# STBlitter_RevA.net
KiCad netlist of a schematic drawn in EAGLE
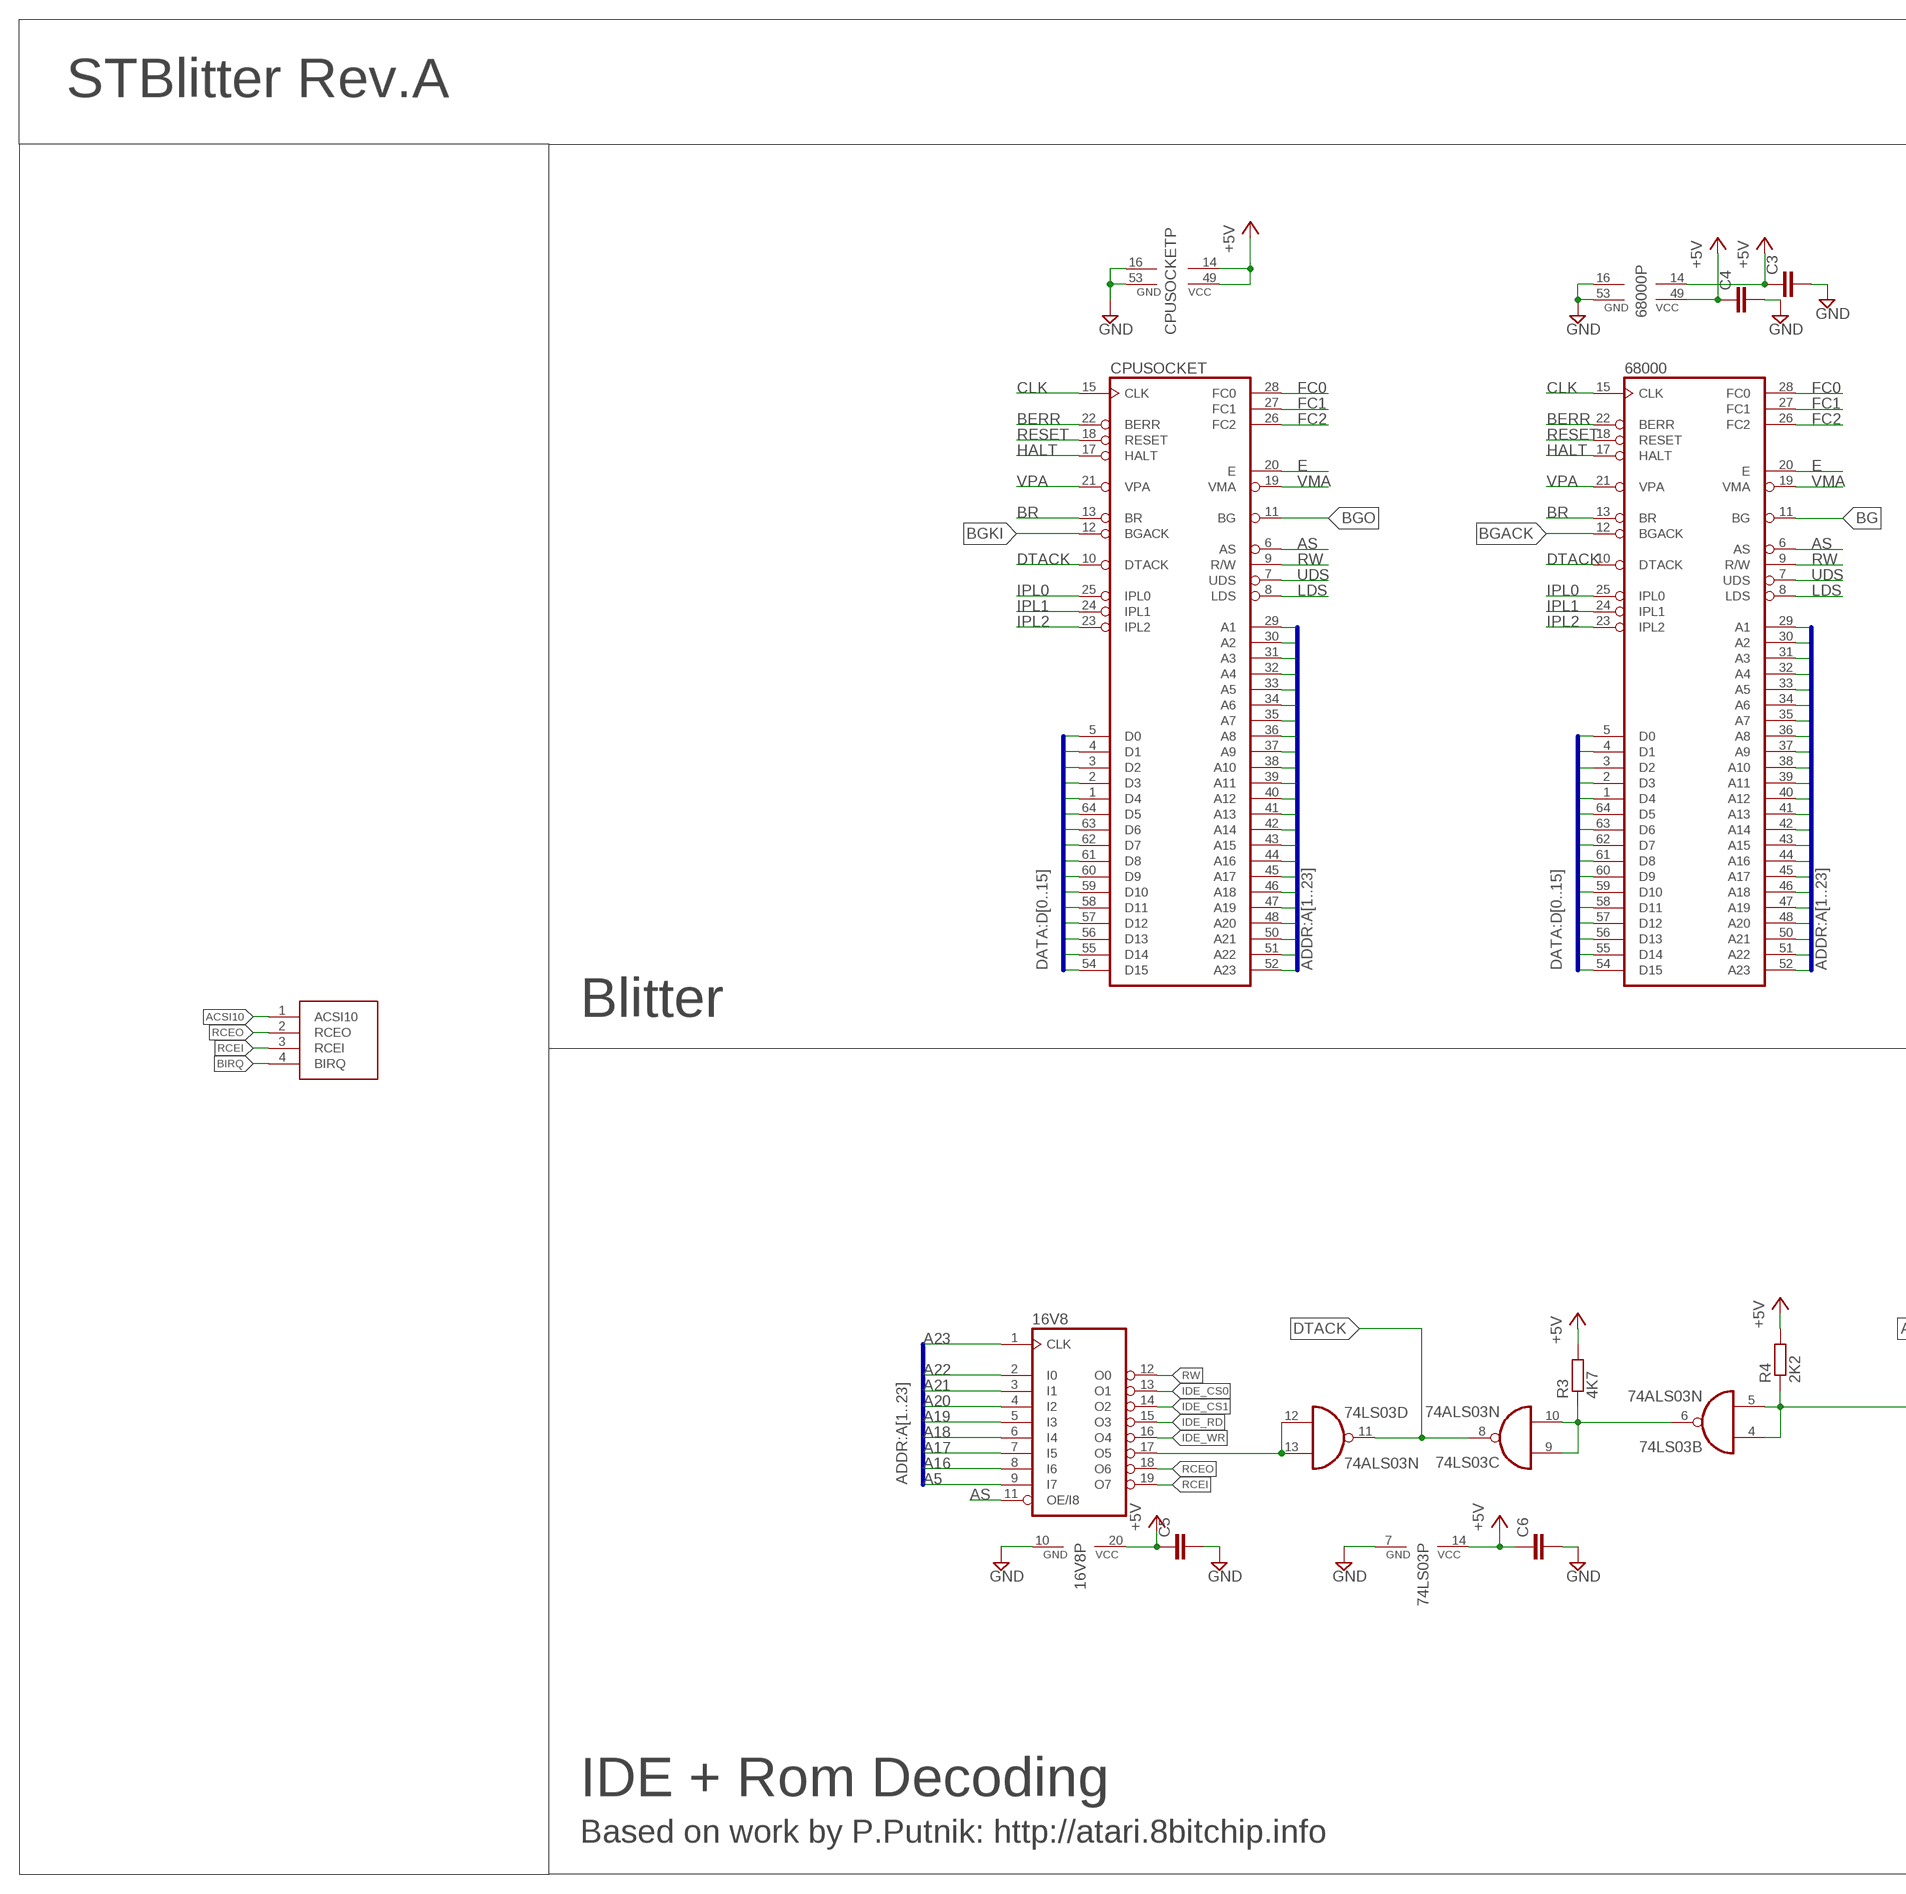
[diagram p0: schematic, sheet 1, part 1 of 2]
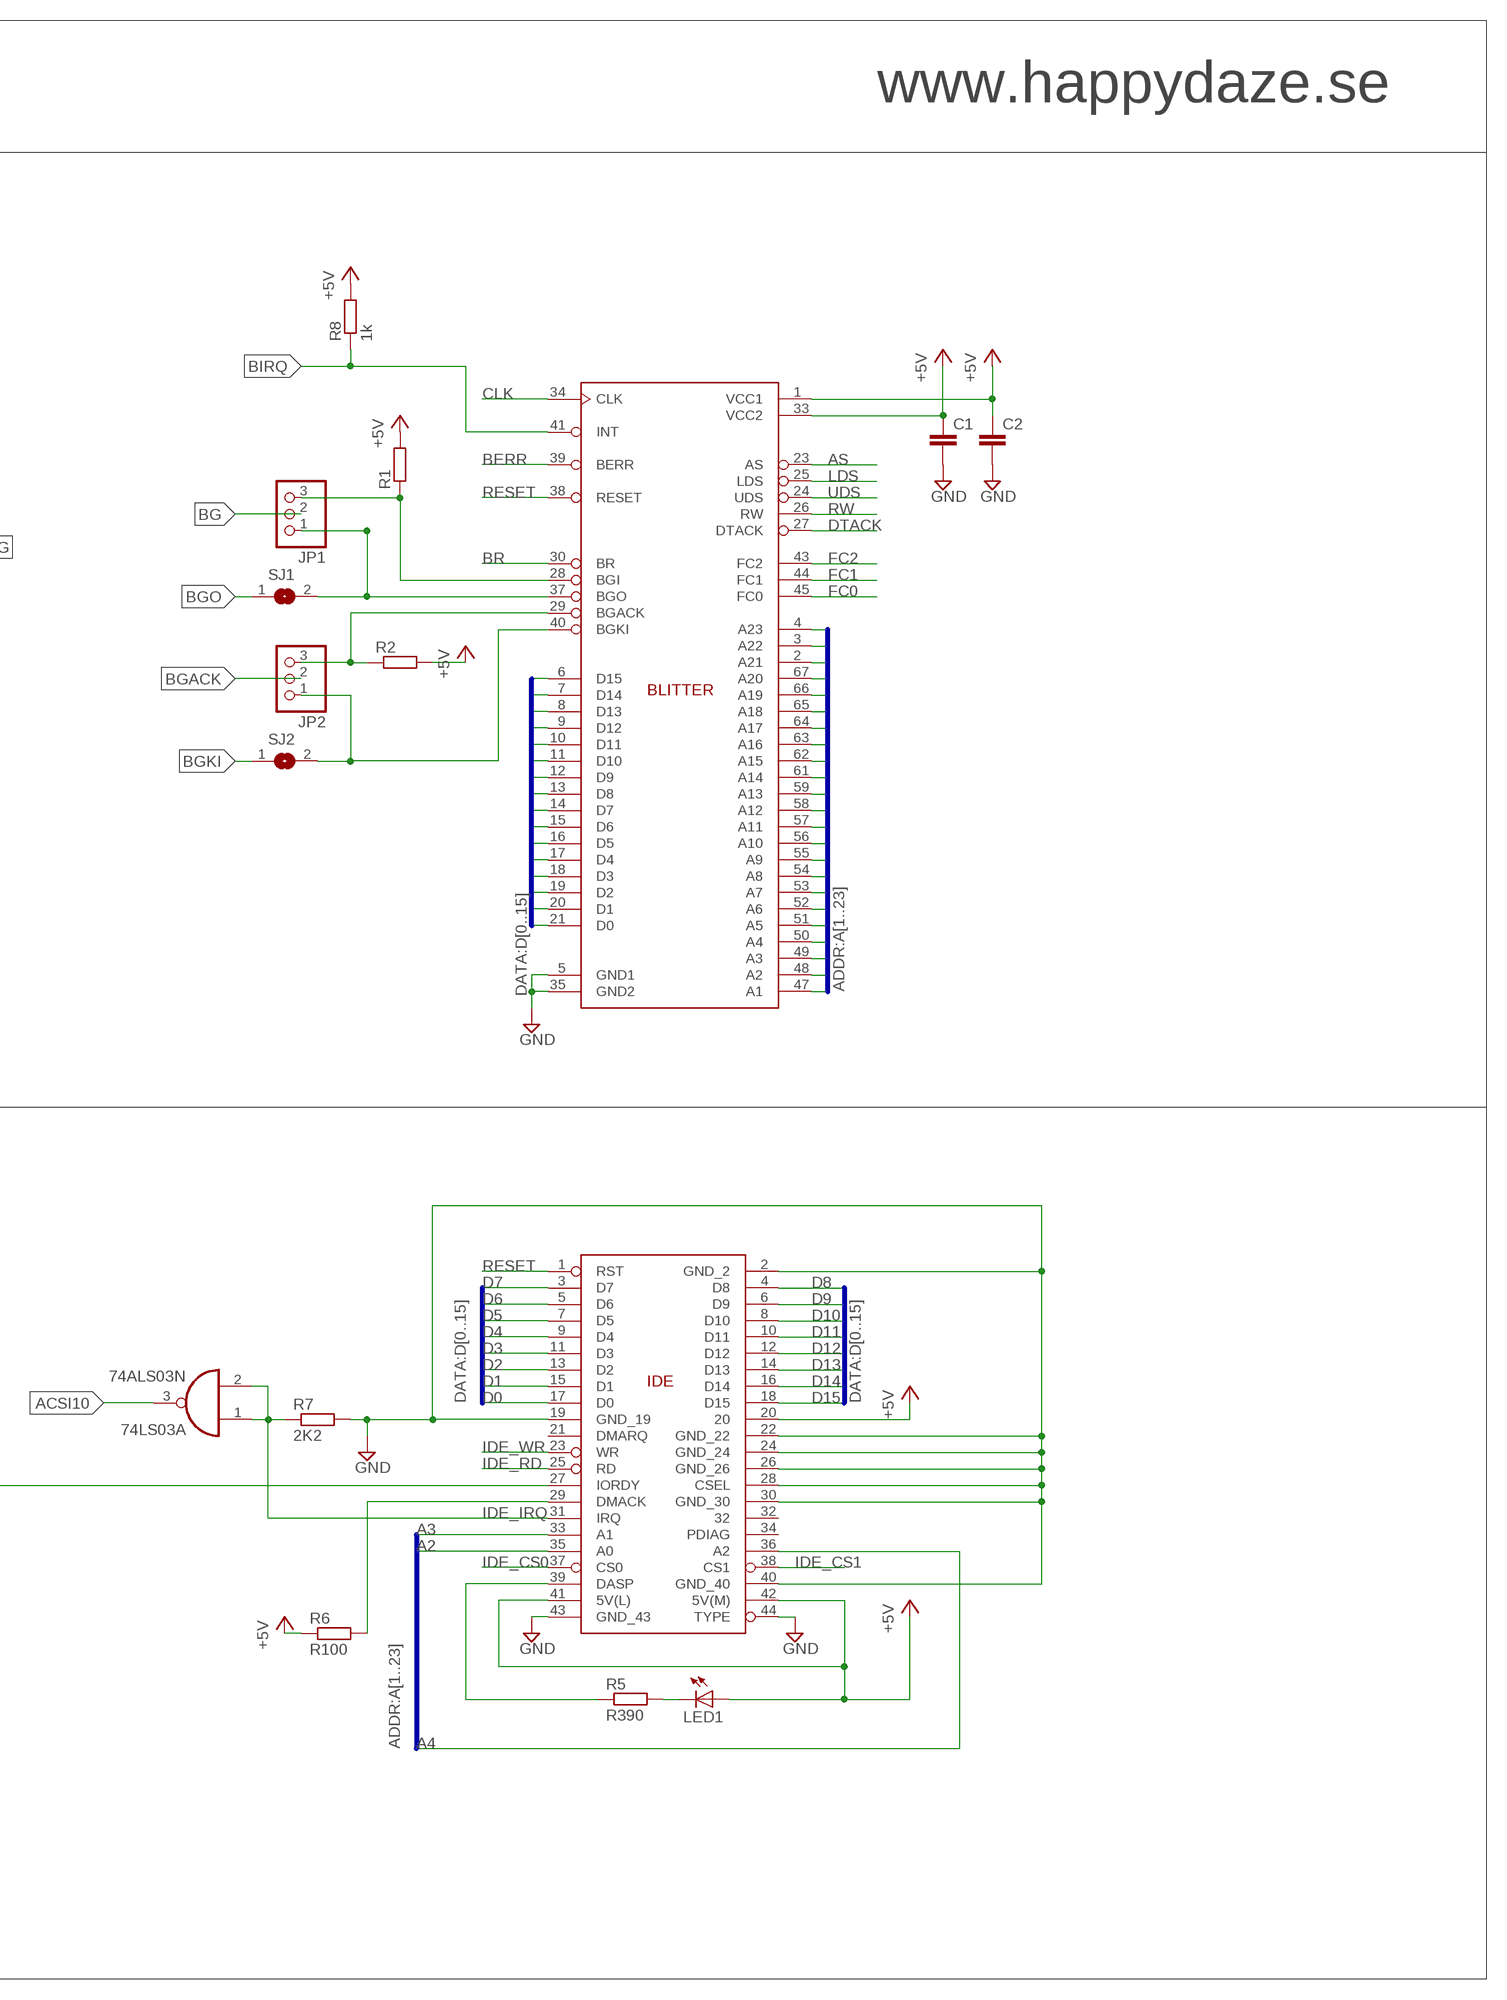
[diagram p1: schematic, sheet 1, part 2 of 2]

(export (version "E")
  (design (tool "Eeschema 10.0.6"))
  (components
    (comp (ref "16V8")
      (value "16V8")
      (footprint "eagle-import:DIL20")
      (fields (field (name "MPN") "GAL16V8D-7LPN"))
      (libsource (lib "eagle-import") (part "16V8"))
    )
    (comp (ref "74LS03")
      (value "74ALS03N")
      (footprint "eagle-import:DIL14")
      (libsource (lib "eagle-import") (part "7403NALS"))
    )
    (comp (ref "68000")
      (value "MC68000P")
      (footprint "eagle-import:DIL64")
      (libsource (lib "eagle-import") (part "micro-mc68000_288_MC68000P"))
    )
    (comp (ref "C1")
      (value "C-EU050-025X075")
      (footprint "eagle-import:C050-025X075")
      (libsource (lib "eagle-import") (part "C-EU050-025X075"))
    )
    (comp (ref "C2")
      (value "C-EU050-025X075")
      (footprint "eagle-import:C050-025X075")
      (libsource (lib "eagle-import") (part "C-EU050-025X075"))
    )
    (comp (ref "C3")
      (value "C-EU050-025X075")
      (footprint "eagle-import:C050-025X075")
      (libsource (lib "eagle-import") (part "C-EU050-025X075"))
    )
    (comp (ref "C4")
      (value "C-EU050-025X075")
      (footprint "eagle-import:C050-025X075")
      (libsource (lib "eagle-import") (part "C-EU050-025X075"))
    )
    (comp (ref "C5")
      (value "C-EU050-025X075")
      (footprint "eagle-import:C050-025X075")
      (libsource (lib "eagle-import") (part "C-EU050-025X075"))
    )
    (comp (ref "C6")
      (value "C-EU050-025X075")
      (footprint "eagle-import:C050-025X075")
      (libsource (lib "eagle-import") (part "C-EU050-025X075"))
    )
    (comp (ref "CFCARD")
      (value "IDE44_CON")
      (footprint "eagle-import:IDE44_CON")
      (libsource (lib "eagle-import") (part "IDE44_CON"))
    )
    (comp (ref "CPUSOCKET")
      (value "MC68000P")
      (footprint "eagle-import:DIL64")
      (libsource (lib "eagle-import") (part "MC68000P"))
    )
    (comp (ref "JP1")
      (value "PINHD-1X3")
      (footprint "eagle-import:1X03")
      (libsource (lib "eagle-import") (part "PINHD-1X3"))
    )
    (comp (ref "JP2")
      (value "PINHD-1X3")
      (footprint "eagle-import:1X03")
      (libsource (lib "eagle-import") (part "PINHD-1X3"))
    )
    (comp (ref "LED1")
      (value "LED3MM")
      (footprint "eagle-import:LED3MM")
      (libsource (lib "eagle-import") (part "LED3MM"))
    )
    (comp (ref "R1")
      (value "R-EU_0207/12")
      (footprint "eagle-import:0207_12")
      (libsource (lib "eagle-import") (part "R-EU_0207/12"))
    )
    (comp (ref "R2")
      (value "R-EU_0207/12")
      (footprint "eagle-import:0207_12")
      (libsource (lib "eagle-import") (part "R-EU_0207/12"))
    )
    (comp (ref "R3")
      (value "4K7")
      (footprint "eagle-import:0207_12")
      (libsource (lib "eagle-import") (part "R-EU_0207/12"))
    )
    (comp (ref "R4")
      (value "2K2")
      (footprint "eagle-import:0207_12")
      (libsource (lib "eagle-import") (part "R-EU_0207/12"))
    )
    (comp (ref "R5")
      (value "R390")
      (footprint "eagle-import:0207_12")
      (libsource (lib "eagle-import") (part "R-EU_0207/12"))
    )
    (comp (ref "R6")
      (value "R100")
      (footprint "eagle-import:0207_12")
      (libsource (lib "eagle-import") (part "R-EU_0207/12"))
    )
    (comp (ref "R7")
      (value "2K2")
      (footprint "eagle-import:0207_12")
      (libsource (lib "eagle-import") (part "R-EU_0207/12"))
    )
    (comp (ref "R8")
      (value "1k")
      (footprint "eagle-import:0207_12")
      (libsource (lib "eagle-import") (part "R-EU_0207/12"))
    )
    (comp (ref "SJ1") (value "SJ") (footprint "eagle-import:SJ") (libsource (lib "eagle-import") (part "SJ")))
    (comp (ref "SJ2") (value "SJ") (footprint "eagle-import:SJ") (libsource (lib "eagle-import") (part "SJ")))
    (comp (ref "U$1")
      (value "STBLITTER")
      (footprint "eagle-import:S68")
      (libsource (lib "eagle-import") (part "STBLITTER"))
    )
    (comp (ref "U$2")
      (value "XCON")
      (footprint "eagle-import:XCON")
      (libsource (lib "eagle-import") (part "XCON"))
    )
  )
  (nets
    (net (code "40") (name "+5V") (class "Default")
      (node (ref "16V8") (pin "20") (pinfunction "VCC_20") (pintype "power_in"))
      (node (ref "68000") (pin "14") (pinfunction "VCC_14") (pintype "power_in"))
      (node (ref "68000") (pin "49") (pinfunction "VCC_49") (pintype "power_in"))
      (node (ref "74LS03") (pin "14") (pinfunction "VCC_14") (pintype "power_in"))
      (node (ref "C1") (pin "1") (pinfunction "1_1") (pintype "passive"))
      (node (ref "C2") (pin "1") (pinfunction "1_1") (pintype "passive"))
      (node (ref "C3") (pin "1") (pinfunction "1_1") (pintype "passive"))
      (node (ref "C4") (pin "1") (pinfunction "1_1") (pintype "passive"))
      (node (ref "C5") (pin "1") (pinfunction "1_1") (pintype "passive"))
      (node (ref "C6") (pin "1") (pinfunction "1_1") (pintype "passive"))
      (node (ref "CFCARD") (pin "20") (pinfunction "20_20") (pintype "bidirectional"))
      (node (ref "CFCARD") (pin "41") (pinfunction "5V(L)_41") (pintype "bidirectional"))
      (node (ref "CFCARD") (pin "42") (pinfunction "5V(M)_42") (pintype "bidirectional"))
      (node (ref "CPUSOCKET") (pin "14") (pinfunction "VCC_14") (pintype "power_in"))
      (node (ref "CPUSOCKET") (pin "49") (pinfunction "VCC_49") (pintype "power_in"))
      (node (ref "LED1") (pin "A") (pinfunction "A_A") (pintype "passive"))
      (node (ref "R1") (pin "2") (pinfunction "2_2") (pintype "passive"))
      (node (ref "R2") (pin "2") (pinfunction "2_2") (pintype "passive"))
      (node (ref "R3") (pin "2") (pinfunction "2_2") (pintype "passive"))
      (node (ref "R4") (pin "2") (pinfunction "2_2") (pintype "passive"))
      (node (ref "R6") (pin "1") (pinfunction "1_1") (pintype "passive"))
      (node (ref "R8") (pin "2") (pinfunction "2_2") (pintype "passive"))
      (node (ref "U$1") (pin "1") (pinfunction "VCC1_1") (pintype "power_in"))
      (node (ref "U$1") (pin "33") (pinfunction "VCC2_33") (pintype "power_in"))
    )
    (net (code "41") (name "/A1") (class "Default")
      (node (ref "68000") (pin "29") (pinfunction "A1_29") (pintype "output"))
      (node (ref "CPUSOCKET") (pin "29") (pinfunction "A1_29") (pintype "output"))
      (node (ref "U$1") (pin "47") (pinfunction "A1_47") (pintype "bidirectional"))
    )
    (net (code "42") (name "/A2") (class "Default")
      (node (ref "68000") (pin "30") (pinfunction "A2_30") (pintype "output"))
      (node (ref "CFCARD") (pin "35") (pinfunction "A0_35") (pintype "bidirectional"))
      (node (ref "CPUSOCKET") (pin "30") (pinfunction "A2_30") (pintype "output"))
      (node (ref "U$1") (pin "48") (pinfunction "A2_48") (pintype "bidirectional"))
    )
    (net (code "43") (name "/A3") (class "Default")
      (node (ref "68000") (pin "31") (pinfunction "A3_31") (pintype "output"))
      (node (ref "CFCARD") (pin "33") (pinfunction "A1_33") (pintype "bidirectional"))
      (node (ref "CPUSOCKET") (pin "31") (pinfunction "A3_31") (pintype "output"))
      (node (ref "U$1") (pin "49") (pinfunction "A3_49") (pintype "bidirectional"))
    )
    (net (code "44") (name "/A4") (class "Default")
      (node (ref "68000") (pin "32") (pinfunction "A4_32") (pintype "output"))
      (node (ref "CFCARD") (pin "36") (pinfunction "A2_36") (pintype "bidirectional"))
      (node (ref "CPUSOCKET") (pin "32") (pinfunction "A4_32") (pintype "output"))
      (node (ref "U$1") (pin "50") (pinfunction "A4_50") (pintype "bidirectional"))
    )
    (net (code "45") (name "/A5") (class "Default")
      (node (ref "16V8") (pin "9") (pinfunction "I7_9") (pintype "input"))
      (node (ref "68000") (pin "33") (pinfunction "A5_33") (pintype "output"))
      (node (ref "CPUSOCKET") (pin "33") (pinfunction "A5_33") (pintype "output"))
      (node (ref "U$1") (pin "51") (pinfunction "A5_51") (pintype "bidirectional"))
    )
    (net (code "46") (name "/A6") (class "Default")
      (node (ref "68000") (pin "34") (pinfunction "A6_34") (pintype "output"))
      (node (ref "CPUSOCKET") (pin "34") (pinfunction "A6_34") (pintype "output"))
      (node (ref "U$1") (pin "52") (pinfunction "A6_52") (pintype "bidirectional"))
    )
    (net (code "47") (name "/A7") (class "Default")
      (node (ref "68000") (pin "35") (pinfunction "A7_35") (pintype "output"))
      (node (ref "CPUSOCKET") (pin "35") (pinfunction "A7_35") (pintype "output"))
      (node (ref "U$1") (pin "53") (pinfunction "A7_53") (pintype "bidirectional"))
    )
    (net (code "48") (name "/A8") (class "Default")
      (node (ref "68000") (pin "36") (pinfunction "A8_36") (pintype "output"))
      (node (ref "CPUSOCKET") (pin "36") (pinfunction "A8_36") (pintype "output"))
      (node (ref "U$1") (pin "54") (pinfunction "A8_54") (pintype "bidirectional"))
    )
    (net (code "49") (name "/A9") (class "Default")
      (node (ref "68000") (pin "37") (pinfunction "A9_37") (pintype "output"))
      (node (ref "CPUSOCKET") (pin "37") (pinfunction "A9_37") (pintype "output"))
      (node (ref "U$1") (pin "55") (pinfunction "A9_55") (pintype "bidirectional"))
    )
    (net (code "50") (name "/A10") (class "Default")
      (node (ref "68000") (pin "38") (pinfunction "A10_38") (pintype "output"))
      (node (ref "CPUSOCKET") (pin "38") (pinfunction "A10_38") (pintype "output"))
      (node (ref "U$1") (pin "56") (pinfunction "A10_56") (pintype "bidirectional"))
    )
    (net (code "51") (name "/A11") (class "Default")
      (node (ref "68000") (pin "39") (pinfunction "A11_39") (pintype "output"))
      (node (ref "CPUSOCKET") (pin "39") (pinfunction "A11_39") (pintype "output"))
      (node (ref "U$1") (pin "57") (pinfunction "A11_57") (pintype "bidirectional"))
    )
    (net (code "52") (name "/A12") (class "Default")
      (node (ref "68000") (pin "40") (pinfunction "A12_40") (pintype "output"))
      (node (ref "CPUSOCKET") (pin "40") (pinfunction "A12_40") (pintype "output"))
      (node (ref "U$1") (pin "58") (pinfunction "A12_58") (pintype "bidirectional"))
    )
    (net (code "53") (name "/A13") (class "Default")
      (node (ref "68000") (pin "41") (pinfunction "A13_41") (pintype "output"))
      (node (ref "CPUSOCKET") (pin "41") (pinfunction "A13_41") (pintype "output"))
      (node (ref "U$1") (pin "59") (pinfunction "A13_59") (pintype "bidirectional"))
    )
    (net (code "54") (name "/A14") (class "Default")
      (node (ref "68000") (pin "42") (pinfunction "A14_42") (pintype "output"))
      (node (ref "CPUSOCKET") (pin "42") (pinfunction "A14_42") (pintype "output"))
      (node (ref "U$1") (pin "61") (pinfunction "A14_61") (pintype "bidirectional"))
    )
    (net (code "55") (name "/A15") (class "Default")
      (node (ref "68000") (pin "43") (pinfunction "A15_43") (pintype "output"))
      (node (ref "CPUSOCKET") (pin "43") (pinfunction "A15_43") (pintype "output"))
      (node (ref "U$1") (pin "62") (pinfunction "A15_62") (pintype "bidirectional"))
    )
    (net (code "56") (name "/A16") (class "Default")
      (node (ref "16V8") (pin "8") (pinfunction "I6_8") (pintype "input"))
      (node (ref "68000") (pin "44") (pinfunction "A16_44") (pintype "output"))
      (node (ref "CPUSOCKET") (pin "44") (pinfunction "A16_44") (pintype "output"))
      (node (ref "U$1") (pin "63") (pinfunction "A16_63") (pintype "bidirectional"))
    )
    (net (code "57") (name "/A17") (class "Default")
      (node (ref "16V8") (pin "7") (pinfunction "I5_7") (pintype "input"))
      (node (ref "68000") (pin "45") (pinfunction "A17_45") (pintype "output"))
      (node (ref "CPUSOCKET") (pin "45") (pinfunction "A17_45") (pintype "output"))
      (node (ref "U$1") (pin "64") (pinfunction "A17_64") (pintype "bidirectional"))
    )
    (net (code "58") (name "/A18") (class "Default")
      (node (ref "16V8") (pin "6") (pinfunction "I4_6") (pintype "input"))
      (node (ref "68000") (pin "46") (pinfunction "A18_46") (pintype "output"))
      (node (ref "CPUSOCKET") (pin "46") (pinfunction "A18_46") (pintype "output"))
      (node (ref "U$1") (pin "65") (pinfunction "A18_65") (pintype "bidirectional"))
    )
    (net (code "59") (name "/A19") (class "Default")
      (node (ref "16V8") (pin "5") (pinfunction "I3_5") (pintype "input"))
      (node (ref "68000") (pin "47") (pinfunction "A19_47") (pintype "output"))
      (node (ref "CPUSOCKET") (pin "47") (pinfunction "A19_47") (pintype "output"))
      (node (ref "U$1") (pin "66") (pinfunction "A19_66") (pintype "bidirectional"))
    )
    (net (code "60") (name "/A20") (class "Default")
      (node (ref "16V8") (pin "4") (pinfunction "I2_4") (pintype "input"))
      (node (ref "68000") (pin "48") (pinfunction "A20_48") (pintype "output"))
      (node (ref "CPUSOCKET") (pin "48") (pinfunction "A20_48") (pintype "output"))
      (node (ref "U$1") (pin "67") (pinfunction "A20_67") (pintype "bidirectional"))
    )
    (net (code "61") (name "/A21") (class "Default")
      (node (ref "16V8") (pin "3") (pinfunction "I1_3") (pintype "input"))
      (node (ref "68000") (pin "50") (pinfunction "A21_50") (pintype "output"))
      (node (ref "CPUSOCKET") (pin "50") (pinfunction "A21_50") (pintype "output"))
      (node (ref "U$1") (pin "2") (pinfunction "A21_2") (pintype "bidirectional"))
    )
    (net (code "62") (name "/A22") (class "Default")
      (node (ref "16V8") (pin "2") (pinfunction "I0_2") (pintype "input"))
      (node (ref "68000") (pin "51") (pinfunction "A22_51") (pintype "output"))
      (node (ref "CPUSOCKET") (pin "51") (pinfunction "A22_51") (pintype "output"))
      (node (ref "U$1") (pin "3") (pinfunction "A22_3") (pintype "bidirectional"))
    )
    (net (code "63") (name "/A23") (class "Default")
      (node (ref "16V8") (pin "1") (pinfunction "CLK_1") (pintype "input"))
      (node (ref "68000") (pin "52") (pinfunction "A23_52") (pintype "output"))
      (node (ref "CPUSOCKET") (pin "52") (pinfunction "A23_52") (pintype "output"))
      (node (ref "U$1") (pin "4") (pinfunction "A23_4") (pintype "bidirectional"))
    )
    (net (code "65") (name "/AS") (class "Default")
      (node (ref "16V8") (pin "11") (pinfunction "OE/I8_11") (pintype "input"))
      (node (ref "68000") (pin "6") (pinfunction "AS_6") (pintype "output"))
      (node (ref "CPUSOCKET") (pin "6") (pinfunction "AS_6") (pintype "output"))
      (node (ref "U$1") (pin "23") (pinfunction "AS_23") (pintype "bidirectional"))
    )
    (net (code "66") (name "/BERR") (class "Default")
      (node (ref "68000") (pin "22") (pinfunction "BERR_22") (pintype "input"))
      (node (ref "CPUSOCKET") (pin "22") (pinfunction "BERR_22") (pintype "input"))
      (node (ref "U$1") (pin "39") (pinfunction "BERR_39") (pintype "bidirectional"))
    )
    (net (code "67") (name "/BR") (class "Default")
      (node (ref "68000") (pin "13") (pinfunction "BR_13") (pintype "input"))
      (node (ref "CPUSOCKET") (pin "13") (pinfunction "BR_13") (pintype "input"))
      (node (ref "U$1") (pin "30") (pinfunction "BR_30") (pintype "bidirectional"))
    )
    (net (code "68") (name "/CLK") (class "Default")
      (node (ref "68000") (pin "15") (pinfunction "CLK_15") (pintype "input"))
      (node (ref "CPUSOCKET") (pin "15") (pinfunction "CLK_15") (pintype "input"))
      (node (ref "U$1") (pin "34") (pinfunction "CLK_34") (pintype "bidirectional"))
    )
    (net (code "69") (name "/D0") (class "Default")
      (node (ref "68000") (pin "5") (pinfunction "D0_5") (pintype "bidirectional"))
      (node (ref "CFCARD") (pin "17") (pinfunction "D0_17") (pintype "bidirectional"))
      (node (ref "CPUSOCKET") (pin "5") (pinfunction "D0_5") (pintype "bidirectional"))
      (node (ref "U$1") (pin "21") (pinfunction "D0_21") (pintype "bidirectional"))
    )
    (net (code "70") (name "/D1") (class "Default")
      (node (ref "68000") (pin "4") (pinfunction "D1_4") (pintype "bidirectional"))
      (node (ref "CFCARD") (pin "15") (pinfunction "D1_15") (pintype "bidirectional"))
      (node (ref "CPUSOCKET") (pin "4") (pinfunction "D1_4") (pintype "bidirectional"))
      (node (ref "U$1") (pin "20") (pinfunction "D1_20") (pintype "bidirectional"))
    )
    (net (code "71") (name "/D2") (class "Default")
      (node (ref "68000") (pin "3") (pinfunction "D2_3") (pintype "bidirectional"))
      (node (ref "CFCARD") (pin "13") (pinfunction "D2_13") (pintype "bidirectional"))
      (node (ref "CPUSOCKET") (pin "3") (pinfunction "D2_3") (pintype "bidirectional"))
      (node (ref "U$1") (pin "19") (pinfunction "D2_19") (pintype "bidirectional"))
    )
    (net (code "72") (name "/D3") (class "Default")
      (node (ref "68000") (pin "2") (pinfunction "D3_2") (pintype "bidirectional"))
      (node (ref "CFCARD") (pin "11") (pinfunction "D3_11") (pintype "bidirectional"))
      (node (ref "CPUSOCKET") (pin "2") (pinfunction "D3_2") (pintype "bidirectional"))
      (node (ref "U$1") (pin "18") (pinfunction "D3_18") (pintype "bidirectional"))
    )
    (net (code "73") (name "/D4") (class "Default")
      (node (ref "68000") (pin "1") (pinfunction "D4_1") (pintype "bidirectional"))
      (node (ref "CFCARD") (pin "9") (pinfunction "D4_9") (pintype "bidirectional"))
      (node (ref "CPUSOCKET") (pin "1") (pinfunction "D4_1") (pintype "bidirectional"))
      (node (ref "U$1") (pin "17") (pinfunction "D4_17") (pintype "bidirectional"))
    )
    (net (code "74") (name "/D5") (class "Default")
      (node (ref "68000") (pin "64") (pinfunction "D5_64") (pintype "bidirectional"))
      (node (ref "CFCARD") (pin "7") (pinfunction "D5_7") (pintype "bidirectional"))
      (node (ref "CPUSOCKET") (pin "64") (pinfunction "D5_64") (pintype "bidirectional"))
      (node (ref "U$1") (pin "16") (pinfunction "D5_16") (pintype "bidirectional"))
    )
    (net (code "75") (name "/D6") (class "Default")
      (node (ref "68000") (pin "63") (pinfunction "D6_63") (pintype "bidirectional"))
      (node (ref "CFCARD") (pin "5") (pinfunction "D6_5") (pintype "bidirectional"))
      (node (ref "CPUSOCKET") (pin "63") (pinfunction "D6_63") (pintype "bidirectional"))
      (node (ref "U$1") (pin "15") (pinfunction "D6_15") (pintype "bidirectional"))
    )
    (net (code "76") (name "/D7") (class "Default")
      (node (ref "68000") (pin "62") (pinfunction "D7_62") (pintype "bidirectional"))
      (node (ref "CFCARD") (pin "3") (pinfunction "D7_3") (pintype "bidirectional"))
      (node (ref "CPUSOCKET") (pin "62") (pinfunction "D7_62") (pintype "bidirectional"))
      (node (ref "U$1") (pin "14") (pinfunction "D7_14") (pintype "bidirectional"))
    )
    (net (code "77") (name "/D8") (class "Default")
      (node (ref "68000") (pin "61") (pinfunction "D8_61") (pintype "bidirectional"))
      (node (ref "CFCARD") (pin "4") (pinfunction "D8_4") (pintype "bidirectional"))
      (node (ref "CPUSOCKET") (pin "61") (pinfunction "D8_61") (pintype "bidirectional"))
      (node (ref "U$1") (pin "13") (pinfunction "D8_13") (pintype "bidirectional"))
    )
    (net (code "78") (name "/D9") (class "Default")
      (node (ref "68000") (pin "60") (pinfunction "D9_60") (pintype "bidirectional"))
      (node (ref "CFCARD") (pin "6") (pinfunction "D9_6") (pintype "bidirectional"))
      (node (ref "CPUSOCKET") (pin "60") (pinfunction "D9_60") (pintype "bidirectional"))
      (node (ref "U$1") (pin "12") (pinfunction "D9_12") (pintype "bidirectional"))
    )
    (net (code "79") (name "/D10") (class "Default")
      (node (ref "68000") (pin "59") (pinfunction "D10_59") (pintype "bidirectional"))
      (node (ref "CFCARD") (pin "8") (pinfunction "D10_8") (pintype "bidirectional"))
      (node (ref "CPUSOCKET") (pin "59") (pinfunction "D10_59") (pintype "bidirectional"))
      (node (ref "U$1") (pin "11") (pinfunction "D10_11") (pintype "bidirectional"))
    )
    (net (code "80") (name "/D11") (class "Default")
      (node (ref "68000") (pin "58") (pinfunction "D11_58") (pintype "bidirectional"))
      (node (ref "CFCARD") (pin "10") (pinfunction "D11_10") (pintype "bidirectional"))
      (node (ref "CPUSOCKET") (pin "58") (pinfunction "D11_58") (pintype "bidirectional"))
      (node (ref "U$1") (pin "10") (pinfunction "D11_10") (pintype "bidirectional"))
    )
    (net (code "81") (name "/D12") (class "Default")
      (node (ref "68000") (pin "57") (pinfunction "D12_57") (pintype "bidirectional"))
      (node (ref "CFCARD") (pin "12") (pinfunction "D12_12") (pintype "bidirectional"))
      (node (ref "CPUSOCKET") (pin "57") (pinfunction "D12_57") (pintype "bidirectional"))
      (node (ref "U$1") (pin "9") (pinfunction "D12_9") (pintype "bidirectional"))
    )
    (net (code "82") (name "/D13") (class "Default")
      (node (ref "68000") (pin "56") (pinfunction "D13_56") (pintype "bidirectional"))
      (node (ref "CFCARD") (pin "14") (pinfunction "D13_14") (pintype "bidirectional"))
      (node (ref "CPUSOCKET") (pin "56") (pinfunction "D13_56") (pintype "bidirectional"))
      (node (ref "U$1") (pin "8") (pinfunction "D13_8") (pintype "bidirectional"))
    )
    (net (code "83") (name "/D14") (class "Default")
      (node (ref "68000") (pin "55") (pinfunction "D14_55") (pintype "bidirectional"))
      (node (ref "CFCARD") (pin "16") (pinfunction "D14_16") (pintype "bidirectional"))
      (node (ref "CPUSOCKET") (pin "55") (pinfunction "D14_55") (pintype "bidirectional"))
      (node (ref "U$1") (pin "7") (pinfunction "D14_7") (pintype "bidirectional"))
    )
    (net (code "84") (name "/D15") (class "Default")
      (node (ref "68000") (pin "54") (pinfunction "D15_54") (pintype "bidirectional"))
      (node (ref "CFCARD") (pin "18") (pinfunction "D15_18") (pintype "bidirectional"))
      (node (ref "CPUSOCKET") (pin "54") (pinfunction "D15_54") (pintype "bidirectional"))
      (node (ref "U$1") (pin "6") (pinfunction "D15_6") (pintype "bidirectional"))
    )
    (net (code "86") (name "/E") (class "Default")
      (node (ref "68000") (pin "20") (pinfunction "E_20") (pintype "output"))
      (node (ref "CPUSOCKET") (pin "20") (pinfunction "E_20") (pintype "output"))
    )
    (net (code "87") (name "/FC0") (class "Default")
      (node (ref "68000") (pin "28") (pinfunction "FC0_28") (pintype "output"))
      (node (ref "CPUSOCKET") (pin "28") (pinfunction "FC0_28") (pintype "output"))
      (node (ref "U$1") (pin "45") (pinfunction "FC0_45") (pintype "bidirectional"))
    )
    (net (code "88") (name "/FC1") (class "Default")
      (node (ref "68000") (pin "27") (pinfunction "FC1_27") (pintype "output"))
      (node (ref "CPUSOCKET") (pin "27") (pinfunction "FC1_27") (pintype "output"))
      (node (ref "U$1") (pin "44") (pinfunction "FC1_44") (pintype "bidirectional"))
    )
    (net (code "89") (name "/FC2") (class "Default")
      (node (ref "68000") (pin "26") (pinfunction "FC2_26") (pintype "output"))
      (node (ref "CPUSOCKET") (pin "26") (pinfunction "FC2_26") (pintype "output"))
      (node (ref "U$1") (pin "43") (pinfunction "FC2_43") (pintype "bidirectional"))
    )
    (net (code "90") (name "/HALT") (class "Default")
      (node (ref "68000") (pin "17") (pinfunction "HALT_17") (pintype "bidirectional"))
      (node (ref "CPUSOCKET") (pin "17") (pinfunction "HALT_17") (pintype "bidirectional"))
    )
    (net (code "91") (name "/IDE_IRQ") (class "Default")
      (node (ref "74LS03") (pin "1") (pinfunction "I0_1") (pintype "input"))
      (node (ref "74LS03") (pin "2") (pinfunction "I1_2") (pintype "input"))
      (node (ref "CFCARD") (pin "31") (pinfunction "IRQ_31") (pintype "bidirectional"))
      (node (ref "R7") (pin "1") (pinfunction "1_1") (pintype "passive"))
    )
    (net (code "92") (name "/IPL0") (class "Default")
      (node (ref "68000") (pin "25") (pinfunction "IPL0_25") (pintype "input"))
      (node (ref "CPUSOCKET") (pin "25") (pinfunction "IPL0_25") (pintype "input"))
    )
    (net (code "93") (name "/IPL1") (class "Default")
      (node (ref "68000") (pin "24") (pinfunction "IPL1_24") (pintype "input"))
      (node (ref "CPUSOCKET") (pin "24") (pinfunction "IPL1_24") (pintype "input"))
    )
    (net (code "94") (name "/IPL2") (class "Default")
      (node (ref "68000") (pin "23") (pinfunction "IPL2_23") (pintype "input"))
      (node (ref "CPUSOCKET") (pin "23") (pinfunction "IPL2_23") (pintype "input"))
    )
    (net (code "95") (name "/LDS") (class "Default")
      (node (ref "68000") (pin "8") (pinfunction "LDS_8") (pintype "output"))
      (node (ref "CPUSOCKET") (pin "8") (pinfunction "LDS_8") (pintype "output"))
      (node (ref "U$1") (pin "25") (pinfunction "LDS_25") (pintype "bidirectional"))
    )
    (net (code "96") (name "/RESET") (class "Default")
      (node (ref "68000") (pin "18") (pinfunction "RESET_18") (pintype "bidirectional"))
      (node (ref "CFCARD") (pin "1") (pinfunction "RST_1") (pintype "bidirectional"))
      (node (ref "CPUSOCKET") (pin "18") (pinfunction "RESET_18") (pintype "bidirectional"))
      (node (ref "U$1") (pin "38") (pinfunction "RESET_38") (pintype "bidirectional"))
    )
    (net (code "97") (name "/UDS") (class "Default")
      (node (ref "68000") (pin "7") (pinfunction "UDS_7") (pintype "output"))
      (node (ref "CPUSOCKET") (pin "7") (pinfunction "UDS_7") (pintype "output"))
      (node (ref "U$1") (pin "24") (pinfunction "UDS_24") (pintype "bidirectional"))
    )
    (net (code "98") (name "/VMA") (class "Default")
      (node (ref "68000") (pin "19") (pinfunction "VMA_19") (pintype "output"))
      (node (ref "CPUSOCKET") (pin "19") (pinfunction "VMA_19") (pintype "output"))
    )
    (net (code "99") (name "/VPA") (class "Default")
      (node (ref "68000") (pin "21") (pinfunction "VPA_21") (pintype "input"))
      (node (ref "CPUSOCKET") (pin "21") (pinfunction "VPA_21") (pintype "input"))
    )
    (net (code "100") (name "ACSI10") (class "Default")
      (node (ref "74LS03") (pin "3") (pinfunction "O_3") (pintype "open_collector"))
      (node (ref "U$2") (pin "1") (pinfunction "ACSI10_1") (pintype "bidirectional"))
    )
    (net (code "101") (name "BG") (class "Default")
      (node (ref "68000") (pin "11") (pinfunction "BG_11") (pintype "output"))
      (node (ref "JP1") (pin "2") (pinfunction "2_2") (pintype "passive"))
    )
    (net (code "102") (name "BGACK") (class "Default")
      (node (ref "68000") (pin "12") (pinfunction "BGACK_12") (pintype "input"))
      (node (ref "JP2") (pin "2") (pinfunction "2_2") (pintype "passive"))
    )
    (net (code "103") (name "BGKI") (class "Default")
      (node (ref "CPUSOCKET") (pin "12") (pinfunction "BGACK_12") (pintype "input"))
      (node (ref "SJ2") (pin "1") (pinfunction "1_1") (pintype "passive"))
    )
    (net (code "104") (name "BGO") (class "Default")
      (node (ref "CPUSOCKET") (pin "11") (pinfunction "BG_11") (pintype "output"))
      (node (ref "SJ1") (pin "1") (pinfunction "1_1") (pintype "passive"))
    )
    (net (code "105") (name "BIRQ") (class "Default")
      (node (ref "R8") (pin "1") (pinfunction "1_1") (pintype "passive"))
      (node (ref "U$1") (pin "41") (pinfunction "INT_41") (pintype "bidirectional"))
      (node (ref "U$2") (pin "4") (pinfunction "BIRQ_4") (pintype "bidirectional"))
    )
    (net (code "106") (name "DTACK") (class "Default")
      (node (ref "68000") (pin "10") (pinfunction "DTACK_10") (pintype "input"))
      (node (ref "74LS03") (pin "11") (pinfunction "O_11") (pintype "open_collector"))
      (node (ref "74LS03") (pin "8") (pinfunction "O_8") (pintype "open_collector"))
      (node (ref "CPUSOCKET") (pin "10") (pinfunction "DTACK_10") (pintype "input"))
      (node (ref "U$1") (pin "27") (pinfunction "DTACK_27") (pintype "bidirectional"))
    )
    (net (code "107") (name "GND") (class "Default")
      (node (ref "16V8") (pin "10") (pinfunction "GND_10") (pintype "power_in"))
      (node (ref "68000") (pin "16") (pinfunction "GND_16") (pintype "power_in"))
      (node (ref "68000") (pin "53") (pinfunction "GND_53") (pintype "power_in"))
      (node (ref "74LS03") (pin "7") (pinfunction "GND_7") (pintype "power_in"))
      (node (ref "C1") (pin "2") (pinfunction "2_2") (pintype "passive"))
      (node (ref "C2") (pin "2") (pinfunction "2_2") (pintype "passive"))
      (node (ref "C3") (pin "2") (pinfunction "2_2") (pintype "passive"))
      (node (ref "C4") (pin "2") (pinfunction "2_2") (pintype "passive"))
      (node (ref "C5") (pin "2") (pinfunction "2_2") (pintype "passive"))
      (node (ref "C6") (pin "2") (pinfunction "2_2") (pintype "passive"))
      (node (ref "CFCARD") (pin "19") (pinfunction "GND_19_19") (pintype "bidirectional"))
      (node (ref "CFCARD") (pin "2") (pinfunction "GND_2_2") (pintype "bidirectional"))
      (node (ref "CFCARD") (pin "22") (pinfunction "GND_22_22") (pintype "bidirectional"))
      (node (ref "CFCARD") (pin "24") (pinfunction "GND_24_24") (pintype "bidirectional"))
      (node (ref "CFCARD") (pin "26") (pinfunction "GND_26_26") (pintype "bidirectional"))
      (node (ref "CFCARD") (pin "28") (pinfunction "CSEL_28") (pintype "bidirectional"))
      (node (ref "CFCARD") (pin "30") (pinfunction "GND_30_30") (pintype "bidirectional"))
      (node (ref "CFCARD") (pin "40") (pinfunction "GND_40_40") (pintype "bidirectional"))
      (node (ref "CFCARD") (pin "43") (pinfunction "GND_43_43") (pintype "bidirectional"))
      (node (ref "CFCARD") (pin "44") (pinfunction "TYPE_44") (pintype "bidirectional"))
      (node (ref "CPUSOCKET") (pin "16") (pinfunction "GND_16") (pintype "power_in"))
      (node (ref "CPUSOCKET") (pin "53") (pinfunction "GND_53") (pintype "power_in"))
      (node (ref "R7") (pin "2") (pinfunction "2_2") (pintype "passive"))
      (node (ref "U$1") (pin "35") (pinfunction "GND2_35") (pintype "bidirectional"))
      (node (ref "U$1") (pin "5") (pinfunction "GND1_5") (pintype "bidirectional"))
    )
    (net (code "108") (name "IDE_CS0") (class "Default")
      (node (ref "16V8") (pin "13") (pinfunction "O1_13") (pintype "bidirectional"))
      (node (ref "CFCARD") (pin "37") (pinfunction "CS0_37") (pintype "bidirectional"))
    )
    (net (code "109") (name "IDE_CS1") (class "Default")
      (node (ref "16V8") (pin "14") (pinfunction "O2_14") (pintype "bidirectional"))
      (node (ref "CFCARD") (pin "38") (pinfunction "CS1_38") (pintype "bidirectional"))
    )
    (net (code "110") (name "IDE_RD") (class "Default")
      (node (ref "16V8") (pin "15") (pinfunction "O3_15") (pintype "bidirectional"))
      (node (ref "CFCARD") (pin "25") (pinfunction "RD_25") (pintype "bidirectional"))
    )
    (net (code "111") (name "IDE_WR") (class "Default")
      (node (ref "16V8") (pin "16") (pinfunction "O4_16") (pintype "bidirectional"))
      (node (ref "CFCARD") (pin "23") (pinfunction "WR_23") (pintype "bidirectional"))
    )
    (net (code "112") (name "Net-(16V8A-O5)") (class "Default")
      (node (ref "16V8") (pin "17") (pinfunction "O5_17") (pintype "bidirectional"))
      (node (ref "74LS03") (pin "12") (pinfunction "I0_12") (pintype "input"))
      (node (ref "74LS03") (pin "13") (pinfunction "I1_13") (pintype "input"))
    )
    (net (code "113") (name "Net-(74LS03B-I0)") (class "Default")
      (node (ref "74LS03") (pin "4") (pinfunction "I0_4") (pintype "input"))
      (node (ref "74LS03") (pin "5") (pinfunction "I1_5") (pintype "input"))
      (node (ref "CFCARD") (pin "27") (pinfunction "IORDY_27") (pintype "bidirectional"))
      (node (ref "R4") (pin "1") (pinfunction "1_1") (pintype "passive"))
    )
    (net (code "114") (name "Net-(74LS03B-O)") (class "Default")
      (node (ref "74LS03") (pin "10") (pinfunction "I1_10") (pintype "input"))
      (node (ref "74LS03") (pin "6") (pinfunction "O_6") (pintype "open_collector"))
      (node (ref "74LS03") (pin "9") (pinfunction "I0_9") (pintype "input"))
      (node (ref "R3") (pin "1") (pinfunction "1_1") (pintype "passive"))
    )
    (net (code "115") (name "Net-(CFCARD-DASP)") (class "Default")
      (node (ref "CFCARD") (pin "39") (pinfunction "DASP_39") (pintype "bidirectional"))
      (node (ref "R5") (pin "1") (pinfunction "1_1") (pintype "passive"))
    )
    (net (code "116") (name "Net-(CFCARD-DMACK)") (class "Default")
      (node (ref "CFCARD") (pin "29") (pinfunction "DMACK_29") (pintype "bidirectional"))
      (node (ref "R6") (pin "2") (pinfunction "2_2") (pintype "passive"))
    )
    (net (code "117") (name "Net-(LED1-C)") (class "Default")
      (node (ref "LED1") (pin "K") (pinfunction "C_K") (pintype "passive"))
      (node (ref "R5") (pin "2") (pinfunction "2_2") (pintype "passive"))
    )
    (net (code "118") (name "Net-(U$1-BGACK)") (class "Default")
      (node (ref "JP2") (pin "3") (pinfunction "3_3") (pintype "passive"))
      (node (ref "R2") (pin "1") (pinfunction "1_1") (pintype "passive"))
      (node (ref "U$1") (pin "29") (pinfunction "BGACK_29") (pintype "bidirectional"))
    )
    (net (code "119") (name "Net-(U$1-BGI)") (class "Default")
      (node (ref "JP1") (pin "3") (pinfunction "3_3") (pintype "passive"))
      (node (ref "R1") (pin "1") (pinfunction "1_1") (pintype "passive"))
      (node (ref "U$1") (pin "28") (pinfunction "BGI_28") (pintype "bidirectional"))
    )
    (net (code "120") (name "Net-(U$1-BGKI)") (class "Default")
      (node (ref "JP2") (pin "1") (pinfunction "1_1") (pintype "passive"))
      (node (ref "SJ2") (pin "2") (pinfunction "2_2") (pintype "passive"))
      (node (ref "U$1") (pin "40") (pinfunction "BGKI_40") (pintype "bidirectional"))
    )
    (net (code "121") (name "Net-(U$1-BGO)") (class "Default")
      (node (ref "JP1") (pin "1") (pinfunction "1_1") (pintype "passive"))
      (node (ref "SJ1") (pin "2") (pinfunction "2_2") (pintype "passive"))
      (node (ref "U$1") (pin "37") (pinfunction "BGO_37") (pintype "bidirectional"))
    )
    (net (code "122") (name "RCEI") (class "Default")
      (node (ref "16V8") (pin "19") (pinfunction "O7_19") (pintype "bidirectional"))
      (node (ref "U$2") (pin "3") (pinfunction "RCEI_3") (pintype "bidirectional"))
    )
    (net (code "123") (name "RCEO") (class "Default")
      (node (ref "16V8") (pin "18") (pinfunction "O6_18") (pintype "bidirectional"))
      (node (ref "U$2") (pin "2") (pinfunction "RCEO_2") (pintype "bidirectional"))
    )
    (net (code "124") (name "RW") (class "Default")
      (node (ref "16V8") (pin "12") (pinfunction "O0_12") (pintype "bidirectional"))
      (node (ref "68000") (pin "9") (pinfunction "R/W_9") (pintype "output"))
      (node (ref "CPUSOCKET") (pin "9") (pinfunction "R/W_9") (pintype "output"))
      (node (ref "U$1") (pin "26") (pinfunction "RW_26") (pintype "bidirectional"))
    )
    (net (code "125") (name "unconnected-(CFCARD-DMARQ-Pad21)") (class "Default")
      (node (ref "CFCARD") (pin "21") (pinfunction "DMARQ_21") (pintype "bidirectional"))
    )
    (net (code "126") (name "unconnected-(CFCARD-PDIAG-Pad34)") (class "Default")
      (node (ref "CFCARD") (pin "34") (pinfunction "PDIAG_34") (pintype "bidirectional"))
    )
    (net (code "127") (name "unconnected-(CFCARD-Pad32)") (class "Default")
      (node (ref "CFCARD") (pin "32") (pinfunction "32_32") (pintype "bidirectional"))
    )
  )
)
